# Analog.net
KiCad netlist of a schematic drawn in Altium Designer
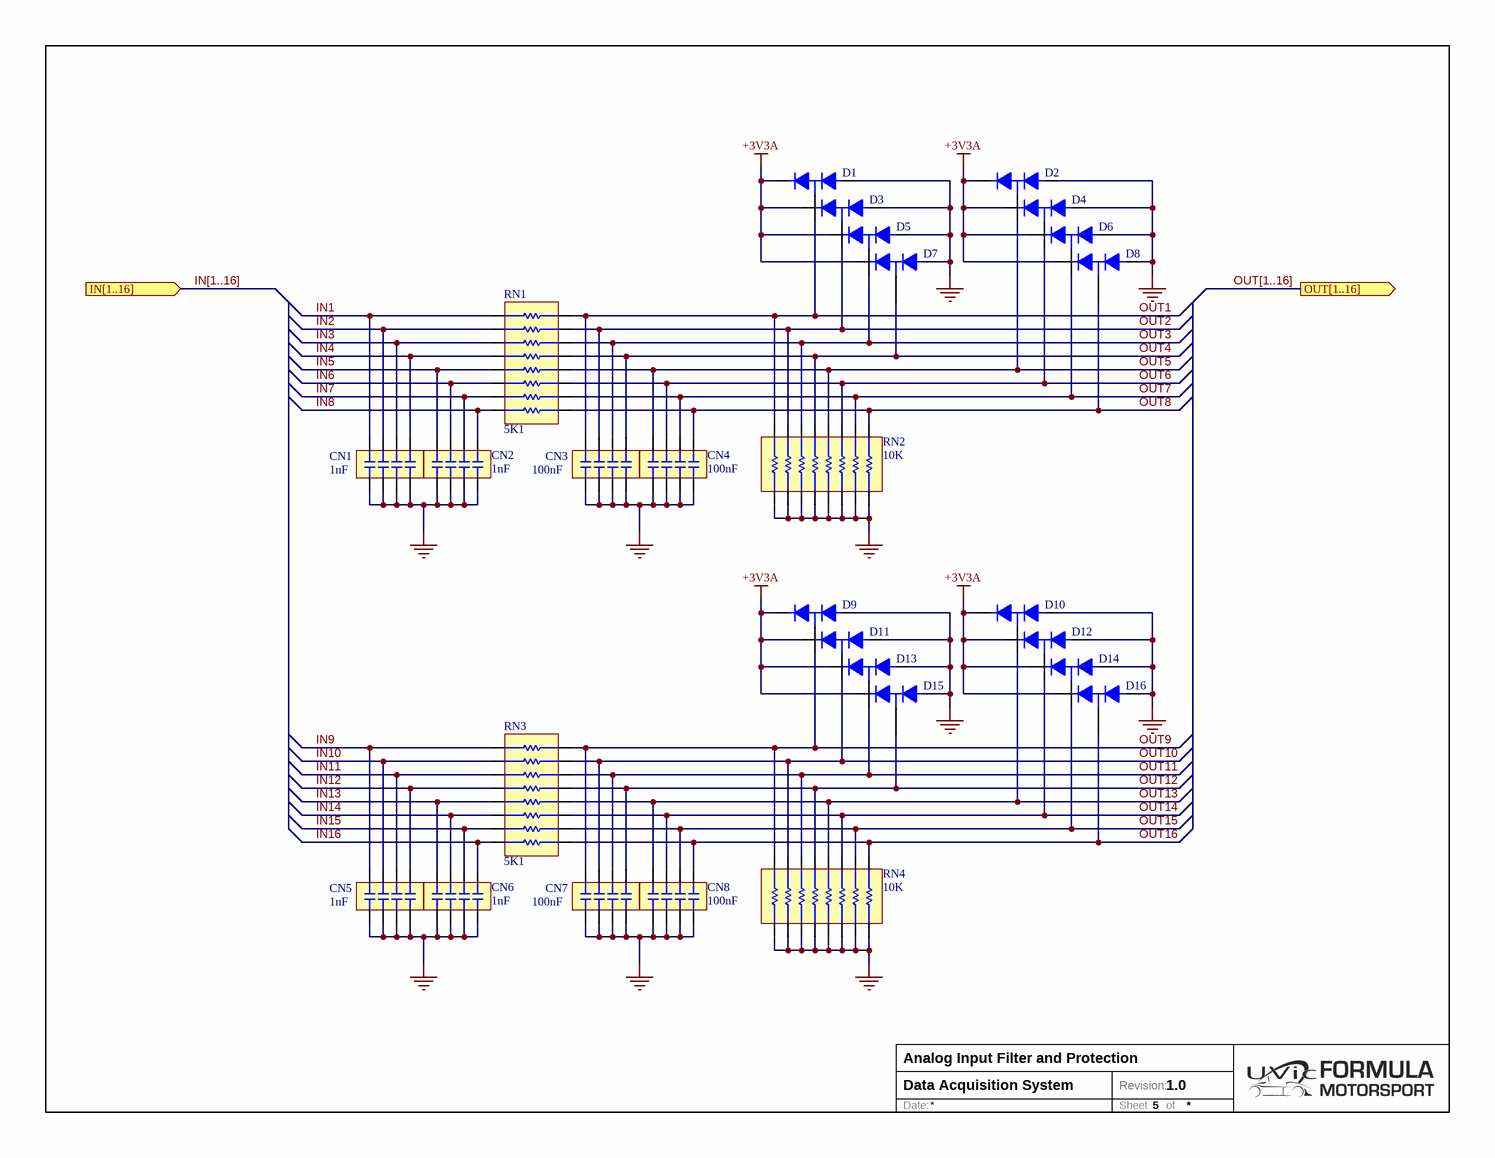
[diagram p0: Analog.SchDoc]

(export (version "E")
  (design (tool "Eeschema 10.0.6"))
  (components
    (comp (ref "CN1")
      (value "1nF")
      (footprint "CAF-80P319X159-8N")
      (description "Capacitor Array - 1nF - 4x - Isolated")
      (fields (field (name "VOLTAGE") "16V") (field (name "Comment") "CKCA43X7R1H102M100AA"))
      (libsource (lib "DAQ") (part "CKCA43X7R1H102M100AA"))
    )
    (comp (ref "CN2")
      (value "1nF")
      (footprint "CAF-80P319X159-8N")
      (description "Capacitor Array - 1nF - 4x - Isolated")
      (fields (field (name "VOLTAGE") "16V") (field (name "Comment") "CKCA43X7R1H102M100AA"))
      (libsource (lib "DAQ") (part "CKCA43X7R1H102M100AA"))
    )
    (comp (ref "CN3")
      (value "100nF")
      (footprint "CAF-80P319X159-8N")
      (description "Capacitor Array - 100nF - 4x - Isolated")
      (fields (field (name "VOLTAGE") "16V") (field (name "Comment") "CKCA43X7R1C104M100AA"))
      (libsource (lib "DAQ") (part "CKCA43X7R1C104M100AA"))
    )
    (comp (ref "CN4")
      (value "100nF")
      (footprint "CAF-80P319X159-8N")
      (description "Capacitor Array - 100nF - 4x - Isolated")
      (fields (field (name "VOLTAGE") "16V") (field (name "Comment") "CKCA43X7R1C104M100AA"))
      (libsource (lib "DAQ") (part "CKCA43X7R1C104M100AA"))
    )
    (comp (ref "CN5")
      (value "1nF")
      (footprint "CAF-80P319X159-8N")
      (description "Capacitor Array - 1nF - 4x - Isolated")
      (fields (field (name "VOLTAGE") "16V") (field (name "Comment") "CKCA43X7R1H102M100AA"))
      (libsource (lib "DAQ") (part "CKCA43X7R1H102M100AA"))
    )
    (comp (ref "CN6")
      (value "1nF")
      (footprint "CAF-80P319X159-8N")
      (description "Capacitor Array - 1nF - 4x - Isolated")
      (fields (field (name "VOLTAGE") "16V") (field (name "Comment") "CKCA43X7R1H102M100AA"))
      (libsource (lib "DAQ") (part "CKCA43X7R1H102M100AA"))
    )
    (comp (ref "CN7")
      (value "100nF")
      (footprint "CAF-80P319X159-8N")
      (description "Capacitor Array - 100nF - 4x - Isolated")
      (fields (field (name "VOLTAGE") "16V") (field (name "Comment") "CKCA43X7R1C104M100AA"))
      (libsource (lib "DAQ") (part "CKCA43X7R1C104M100AA"))
    )
    (comp (ref "CN8")
      (value "100nF")
      (footprint "CAF-80P319X159-8N")
      (description "Capacitor Array - 100nF - 4x - Isolated")
      (fields (field (name "VOLTAGE") "16V") (field (name "Comment") "CKCA43X7R1C104M100AA"))
      (libsource (lib "DAQ") (part "CKCA43X7R1C104M100AA"))
    )
    (comp (ref "D1")
      (value "BAS70-04LT1G")
      (footprint "ONSC-SOT-23-3-318-08_V")
      (description "Schottky Diode Array")
      (libsource (lib "DAQ") (part "BAS70-04LT1G"))
    )
    (comp (ref "D2")
      (value "BAS70-04LT1G")
      (footprint "ONSC-SOT-23-3-318-08_V")
      (description "Schottky Diode Array")
      (libsource (lib "DAQ") (part "BAS70-04LT1G"))
    )
    (comp (ref "D3")
      (value "BAS70-04LT1G")
      (footprint "ONSC-SOT-23-3-318-08_V")
      (description "Schottky Diode Array")
      (libsource (lib "DAQ") (part "BAS70-04LT1G"))
    )
    (comp (ref "D4")
      (value "BAS70-04LT1G")
      (footprint "ONSC-SOT-23-3-318-08_V")
      (description "Schottky Diode Array")
      (libsource (lib "DAQ") (part "BAS70-04LT1G"))
    )
    (comp (ref "D5")
      (value "BAS70-04LT1G")
      (footprint "ONSC-SOT-23-3-318-08_V")
      (description "Schottky Diode Array")
      (libsource (lib "DAQ") (part "BAS70-04LT1G"))
    )
    (comp (ref "D6")
      (value "BAS70-04LT1G")
      (footprint "ONSC-SOT-23-3-318-08_V")
      (description "Schottky Diode Array")
      (libsource (lib "DAQ") (part "BAS70-04LT1G"))
    )
    (comp (ref "D7")
      (value "BAS70-04LT1G")
      (footprint "ONSC-SOT-23-3-318-08_V")
      (description "Schottky Diode Array")
      (libsource (lib "DAQ") (part "BAS70-04LT1G"))
    )
    (comp (ref "D8")
      (value "BAS70-04LT1G")
      (footprint "ONSC-SOT-23-3-318-08_V")
      (description "Schottky Diode Array")
      (libsource (lib "DAQ") (part "BAS70-04LT1G"))
    )
    (comp (ref "D9")
      (value "BAS70-04LT1G")
      (footprint "ONSC-SOT-23-3-318-08_V")
      (description "Schottky Diode Array")
      (libsource (lib "DAQ") (part "BAS70-04LT1G"))
    )
    (comp (ref "D10")
      (value "BAS70-04LT1G")
      (footprint "ONSC-SOT-23-3-318-08_V")
      (description "Schottky Diode Array")
      (libsource (lib "DAQ") (part "BAS70-04LT1G"))
    )
    (comp (ref "D11")
      (value "BAS70-04LT1G")
      (footprint "ONSC-SOT-23-3-318-08_V")
      (description "Schottky Diode Array")
      (libsource (lib "DAQ") (part "BAS70-04LT1G"))
    )
    (comp (ref "D12")
      (value "BAS70-04LT1G")
      (footprint "ONSC-SOT-23-3-318-08_V")
      (description "Schottky Diode Array")
      (libsource (lib "DAQ") (part "BAS70-04LT1G"))
    )
    (comp (ref "D13")
      (value "BAS70-04LT1G")
      (footprint "ONSC-SOT-23-3-318-08_V")
      (description "Schottky Diode Array")
      (libsource (lib "DAQ") (part "BAS70-04LT1G"))
    )
    (comp (ref "D14")
      (value "BAS70-04LT1G")
      (footprint "ONSC-SOT-23-3-318-08_V")
      (description "Schottky Diode Array")
      (libsource (lib "DAQ") (part "BAS70-04LT1G"))
    )
    (comp (ref "D15")
      (value "BAS70-04LT1G")
      (footprint "ONSC-SOT-23-3-318-08_V")
      (description "Schottky Diode Array")
      (libsource (lib "DAQ") (part "BAS70-04LT1G"))
    )
    (comp (ref "D16")
      (value "BAS70-04LT1G")
      (footprint "ONSC-SOT-23-3-318-08_V")
      (description "Schottky Diode Array")
      (libsource (lib "DAQ") (part "BAS70-04LT1G"))
    )
    (comp (ref "RN1")
      (value "5K1")
      (footprint "CAF-80P160X100-8N")
      (description "Resistor Array - 5K1 - x8 - Independent")
      (fields (field (name "TOLERANCE") "5%") (field (name "Comment") "MNR18ERAPJ512"))
      (libsource (lib "DAQ") (part "MNR18ERAPJ512"))
    )
    (comp (ref "RN2")
      (value "10K")
      (footprint "CAF-80P160X100-8N")
      (description "Resistor Array - 10K - x8 - Independent")
      (fields (field (name "TOLERANCE") "5%") (field (name "Comment") "MNR18ERAPJ103"))
      (libsource (lib "DAQ") (part "MNR18ERAPJ103"))
    )
    (comp (ref "RN3")
      (value "5K1")
      (footprint "CAF-80P160X100-8N")
      (description "Resistor Array - 5K1 - x8 - Independent")
      (fields (field (name "TOLERANCE") "5%") (field (name "Comment") "MNR18ERAPJ512"))
      (libsource (lib "DAQ") (part "MNR18ERAPJ512"))
    )
    (comp (ref "RN4")
      (value "10K")
      (footprint "CAF-80P160X100-8N")
      (description "Resistor Array - 10K - x8 - Independent")
      (fields (field (name "TOLERANCE") "5%") (field (name "Comment") "MNR18ERAPJ103"))
      (libsource (lib "DAQ") (part "MNR18ERAPJ103"))
    )
  )
  (nets
    (net (code "1") (name "+3V3A") (class "Default")
      (node (ref "D1") (pin "2") (pinfunction "K_2") (pintype "passive"))
      (node (ref "D10") (pin "2") (pinfunction "K_2") (pintype "passive"))
      (node (ref "D11") (pin "2") (pinfunction "K_2") (pintype "passive"))
      (node (ref "D12") (pin "2") (pinfunction "K_2") (pintype "passive"))
      (node (ref "D13") (pin "2") (pinfunction "K_2") (pintype "passive"))
      (node (ref "D14") (pin "2") (pinfunction "K_2") (pintype "passive"))
      (node (ref "D15") (pin "2") (pinfunction "K_2") (pintype "passive"))
      (node (ref "D16") (pin "2") (pinfunction "K_2") (pintype "passive"))
      (node (ref "D2") (pin "2") (pinfunction "K_2") (pintype "passive"))
      (node (ref "D3") (pin "2") (pinfunction "K_2") (pintype "passive"))
      (node (ref "D4") (pin "2") (pinfunction "K_2") (pintype "passive"))
      (node (ref "D5") (pin "2") (pinfunction "K_2") (pintype "passive"))
      (node (ref "D6") (pin "2") (pinfunction "K_2") (pintype "passive"))
      (node (ref "D7") (pin "2") (pinfunction "K_2") (pintype "passive"))
      (node (ref "D8") (pin "2") (pinfunction "K_2") (pintype "passive"))
      (node (ref "D9") (pin "2") (pinfunction "K_2") (pintype "passive"))
    )
    (net (code "2") (name "/IN1") (class "Default")
      (node (ref "CN1") (pin "8") (pinfunction "8_8") (pintype "passive"))
      (node (ref "RN1") (pin "9") (pinfunction "9_9") (pintype "passive"))
    )
    (net (code "3") (name "/IN2") (class "Default")
      (node (ref "CN1") (pin "7") (pinfunction "7_7") (pintype "passive"))
      (node (ref "RN1") (pin "10") (pinfunction "10_10") (pintype "passive"))
    )
    (net (code "4") (name "/IN3") (class "Default")
      (node (ref "CN1") (pin "6") (pinfunction "6_6") (pintype "passive"))
      (node (ref "RN1") (pin "11") (pinfunction "11_11") (pintype "passive"))
    )
    (net (code "5") (name "/IN4") (class "Default")
      (node (ref "CN1") (pin "5") (pinfunction "5_5") (pintype "passive"))
      (node (ref "RN1") (pin "12") (pinfunction "12_12") (pintype "passive"))
    )
    (net (code "6") (name "/IN5") (class "Default")
      (node (ref "CN2") (pin "8") (pinfunction "8_8") (pintype "passive"))
      (node (ref "RN1") (pin "13") (pinfunction "13_13") (pintype "passive"))
    )
    (net (code "7") (name "/IN6") (class "Default")
      (node (ref "CN2") (pin "7") (pinfunction "7_7") (pintype "passive"))
      (node (ref "RN1") (pin "14") (pinfunction "14_14") (pintype "passive"))
    )
    (net (code "8") (name "/IN7") (class "Default")
      (node (ref "CN2") (pin "6") (pinfunction "6_6") (pintype "passive"))
      (node (ref "RN1") (pin "15") (pinfunction "15_15") (pintype "passive"))
    )
    (net (code "9") (name "/IN8") (class "Default")
      (node (ref "CN2") (pin "5") (pinfunction "5_5") (pintype "passive"))
      (node (ref "RN1") (pin "16") (pinfunction "16_16") (pintype "passive"))
    )
    (net (code "10") (name "/IN9") (class "Default")
      (node (ref "CN5") (pin "8") (pinfunction "8_8") (pintype "passive"))
      (node (ref "RN3") (pin "9") (pinfunction "9_9") (pintype "passive"))
    )
    (net (code "11") (name "/IN10") (class "Default")
      (node (ref "CN5") (pin "7") (pinfunction "7_7") (pintype "passive"))
      (node (ref "RN3") (pin "10") (pinfunction "10_10") (pintype "passive"))
    )
    (net (code "12") (name "/IN11") (class "Default")
      (node (ref "CN5") (pin "6") (pinfunction "6_6") (pintype "passive"))
      (node (ref "RN3") (pin "11") (pinfunction "11_11") (pintype "passive"))
    )
    (net (code "13") (name "/IN12") (class "Default")
      (node (ref "CN5") (pin "5") (pinfunction "5_5") (pintype "passive"))
      (node (ref "RN3") (pin "12") (pinfunction "12_12") (pintype "passive"))
    )
    (net (code "14") (name "/IN13") (class "Default")
      (node (ref "CN6") (pin "8") (pinfunction "8_8") (pintype "passive"))
      (node (ref "RN3") (pin "13") (pinfunction "13_13") (pintype "passive"))
    )
    (net (code "15") (name "/IN14") (class "Default")
      (node (ref "CN6") (pin "7") (pinfunction "7_7") (pintype "passive"))
      (node (ref "RN3") (pin "14") (pinfunction "14_14") (pintype "passive"))
    )
    (net (code "16") (name "/IN15") (class "Default")
      (node (ref "CN6") (pin "6") (pinfunction "6_6") (pintype "passive"))
      (node (ref "RN3") (pin "15") (pinfunction "15_15") (pintype "passive"))
    )
    (net (code "17") (name "/IN16") (class "Default")
      (node (ref "CN6") (pin "5") (pinfunction "5_5") (pintype "passive"))
      (node (ref "RN3") (pin "16") (pinfunction "16_16") (pintype "passive"))
    )
    (net (code "19") (name "/OUT1") (class "Default")
      (node (ref "CN3") (pin "8") (pinfunction "8_8") (pintype "passive"))
      (node (ref "D1") (pin "3") (pinfunction "K/A_3") (pintype "passive"))
      (node (ref "RN1") (pin "8") (pinfunction "8_8") (pintype "passive"))
      (node (ref "RN2") (pin "8") (pinfunction "8_8") (pintype "passive"))
    )
    (net (code "20") (name "/OUT2") (class "Default")
      (node (ref "CN3") (pin "7") (pinfunction "7_7") (pintype "passive"))
      (node (ref "D3") (pin "3") (pinfunction "K/A_3") (pintype "passive"))
      (node (ref "RN1") (pin "7") (pinfunction "7_7") (pintype "passive"))
      (node (ref "RN2") (pin "7") (pinfunction "7_7") (pintype "passive"))
    )
    (net (code "21") (name "/OUT3") (class "Default")
      (node (ref "CN3") (pin "6") (pinfunction "6_6") (pintype "passive"))
      (node (ref "D5") (pin "3") (pinfunction "K/A_3") (pintype "passive"))
      (node (ref "RN1") (pin "6") (pinfunction "6_6") (pintype "passive"))
      (node (ref "RN2") (pin "6") (pinfunction "6_6") (pintype "passive"))
    )
    (net (code "22") (name "/OUT4") (class "Default")
      (node (ref "CN3") (pin "5") (pinfunction "5_5") (pintype "passive"))
      (node (ref "D7") (pin "3") (pinfunction "K/A_3") (pintype "passive"))
      (node (ref "RN1") (pin "5") (pinfunction "5_5") (pintype "passive"))
      (node (ref "RN2") (pin "5") (pinfunction "5_5") (pintype "passive"))
    )
    (net (code "23") (name "/OUT5") (class "Default")
      (node (ref "CN4") (pin "8") (pinfunction "8_8") (pintype "passive"))
      (node (ref "D2") (pin "3") (pinfunction "K/A_3") (pintype "passive"))
      (node (ref "RN1") (pin "4") (pinfunction "4_4") (pintype "passive"))
      (node (ref "RN2") (pin "4") (pinfunction "4_4") (pintype "passive"))
    )
    (net (code "24") (name "/OUT6") (class "Default")
      (node (ref "CN4") (pin "7") (pinfunction "7_7") (pintype "passive"))
      (node (ref "D4") (pin "3") (pinfunction "K/A_3") (pintype "passive"))
      (node (ref "RN1") (pin "3") (pinfunction "3_3") (pintype "passive"))
      (node (ref "RN2") (pin "3") (pinfunction "3_3") (pintype "passive"))
    )
    (net (code "25") (name "/OUT7") (class "Default")
      (node (ref "CN4") (pin "6") (pinfunction "6_6") (pintype "passive"))
      (node (ref "D6") (pin "3") (pinfunction "K/A_3") (pintype "passive"))
      (node (ref "RN1") (pin "2") (pinfunction "2_2") (pintype "passive"))
      (node (ref "RN2") (pin "2") (pinfunction "2_2") (pintype "passive"))
    )
    (net (code "26") (name "/OUT8") (class "Default")
      (node (ref "CN4") (pin "5") (pinfunction "5_5") (pintype "passive"))
      (node (ref "D8") (pin "3") (pinfunction "K/A_3") (pintype "passive"))
      (node (ref "RN1") (pin "1") (pinfunction "1_1") (pintype "passive"))
      (node (ref "RN2") (pin "1") (pinfunction "1_1") (pintype "passive"))
    )
    (net (code "27") (name "/OUT9") (class "Default")
      (node (ref "CN7") (pin "8") (pinfunction "8_8") (pintype "passive"))
      (node (ref "D9") (pin "3") (pinfunction "K/A_3") (pintype "passive"))
      (node (ref "RN3") (pin "8") (pinfunction "8_8") (pintype "passive"))
      (node (ref "RN4") (pin "8") (pinfunction "8_8") (pintype "passive"))
    )
    (net (code "28") (name "/OUT10") (class "Default")
      (node (ref "CN7") (pin "7") (pinfunction "7_7") (pintype "passive"))
      (node (ref "D11") (pin "3") (pinfunction "K/A_3") (pintype "passive"))
      (node (ref "RN3") (pin "7") (pinfunction "7_7") (pintype "passive"))
      (node (ref "RN4") (pin "7") (pinfunction "7_7") (pintype "passive"))
    )
    (net (code "29") (name "/OUT11") (class "Default")
      (node (ref "CN7") (pin "6") (pinfunction "6_6") (pintype "passive"))
      (node (ref "D13") (pin "3") (pinfunction "K/A_3") (pintype "passive"))
      (node (ref "RN3") (pin "6") (pinfunction "6_6") (pintype "passive"))
      (node (ref "RN4") (pin "6") (pinfunction "6_6") (pintype "passive"))
    )
    (net (code "30") (name "/OUT12") (class "Default")
      (node (ref "CN7") (pin "5") (pinfunction "5_5") (pintype "passive"))
      (node (ref "D15") (pin "3") (pinfunction "K/A_3") (pintype "passive"))
      (node (ref "RN3") (pin "5") (pinfunction "5_5") (pintype "passive"))
      (node (ref "RN4") (pin "5") (pinfunction "5_5") (pintype "passive"))
    )
    (net (code "31") (name "/OUT13") (class "Default")
      (node (ref "CN8") (pin "8") (pinfunction "8_8") (pintype "passive"))
      (node (ref "D10") (pin "3") (pinfunction "K/A_3") (pintype "passive"))
      (node (ref "RN3") (pin "4") (pinfunction "4_4") (pintype "passive"))
      (node (ref "RN4") (pin "4") (pinfunction "4_4") (pintype "passive"))
    )
    (net (code "32") (name "/OUT14") (class "Default")
      (node (ref "CN8") (pin "7") (pinfunction "7_7") (pintype "passive"))
      (node (ref "D12") (pin "3") (pinfunction "K/A_3") (pintype "passive"))
      (node (ref "RN3") (pin "3") (pinfunction "3_3") (pintype "passive"))
      (node (ref "RN4") (pin "3") (pinfunction "3_3") (pintype "passive"))
    )
    (net (code "33") (name "/OUT15") (class "Default")
      (node (ref "CN8") (pin "6") (pinfunction "6_6") (pintype "passive"))
      (node (ref "D14") (pin "3") (pinfunction "K/A_3") (pintype "passive"))
      (node (ref "RN3") (pin "2") (pinfunction "2_2") (pintype "passive"))
      (node (ref "RN4") (pin "2") (pinfunction "2_2") (pintype "passive"))
    )
    (net (code "34") (name "/OUT16") (class "Default")
      (node (ref "CN8") (pin "5") (pinfunction "5_5") (pintype "passive"))
      (node (ref "D16") (pin "3") (pinfunction "K/A_3") (pintype "passive"))
      (node (ref "RN3") (pin "1") (pinfunction "1_1") (pintype "passive"))
      (node (ref "RN4") (pin "1") (pinfunction "1_1") (pintype "passive"))
    )
    (net (code "36") (name "GND") (class "Default")
      (node (ref "CN1") (pin "1") (pinfunction "1_1") (pintype "passive"))
      (node (ref "CN1") (pin "2") (pinfunction "2_2") (pintype "passive"))
      (node (ref "CN1") (pin "3") (pinfunction "3_3") (pintype "passive"))
      (node (ref "CN1") (pin "4") (pinfunction "4_4") (pintype "passive"))
      (node (ref "CN2") (pin "1") (pinfunction "1_1") (pintype "passive"))
      (node (ref "CN2") (pin "2") (pinfunction "2_2") (pintype "passive"))
      (node (ref "CN2") (pin "3") (pinfunction "3_3") (pintype "passive"))
      (node (ref "CN2") (pin "4") (pinfunction "4_4") (pintype "passive"))
      (node (ref "CN3") (pin "1") (pinfunction "1_1") (pintype "passive"))
      (node (ref "CN3") (pin "2") (pinfunction "2_2") (pintype "passive"))
      (node (ref "CN3") (pin "3") (pinfunction "3_3") (pintype "passive"))
      (node (ref "CN3") (pin "4") (pinfunction "4_4") (pintype "passive"))
      (node (ref "CN4") (pin "1") (pinfunction "1_1") (pintype "passive"))
      (node (ref "CN4") (pin "2") (pinfunction "2_2") (pintype "passive"))
      (node (ref "CN4") (pin "3") (pinfunction "3_3") (pintype "passive"))
      (node (ref "CN4") (pin "4") (pinfunction "4_4") (pintype "passive"))
      (node (ref "CN5") (pin "1") (pinfunction "1_1") (pintype "passive"))
      (node (ref "CN5") (pin "2") (pinfunction "2_2") (pintype "passive"))
      (node (ref "CN5") (pin "3") (pinfunction "3_3") (pintype "passive"))
      (node (ref "CN5") (pin "4") (pinfunction "4_4") (pintype "passive"))
      (node (ref "CN6") (pin "1") (pinfunction "1_1") (pintype "passive"))
      (node (ref "CN6") (pin "2") (pinfunction "2_2") (pintype "passive"))
      (node (ref "CN6") (pin "3") (pinfunction "3_3") (pintype "passive"))
      (node (ref "CN6") (pin "4") (pinfunction "4_4") (pintype "passive"))
      (node (ref "CN7") (pin "1") (pinfunction "1_1") (pintype "passive"))
      (node (ref "CN7") (pin "2") (pinfunction "2_2") (pintype "passive"))
      (node (ref "CN7") (pin "3") (pinfunction "3_3") (pintype "passive"))
      (node (ref "CN7") (pin "4") (pinfunction "4_4") (pintype "passive"))
      (node (ref "CN8") (pin "1") (pinfunction "1_1") (pintype "passive"))
      (node (ref "CN8") (pin "2") (pinfunction "2_2") (pintype "passive"))
      (node (ref "CN8") (pin "3") (pinfunction "3_3") (pintype "passive"))
      (node (ref "CN8") (pin "4") (pinfunction "4_4") (pintype "passive"))
      (node (ref "D1") (pin "1") (pinfunction "A_1") (pintype "passive"))
      (node (ref "D10") (pin "1") (pinfunction "A_1") (pintype "passive"))
      (node (ref "D11") (pin "1") (pinfunction "A_1") (pintype "passive"))
      (node (ref "D12") (pin "1") (pinfunction "A_1") (pintype "passive"))
      (node (ref "D13") (pin "1") (pinfunction "A_1") (pintype "passive"))
      (node (ref "D14") (pin "1") (pinfunction "A_1") (pintype "passive"))
      (node (ref "D15") (pin "1") (pinfunction "A_1") (pintype "passive"))
      (node (ref "D16") (pin "1") (pinfunction "A_1") (pintype "passive"))
      (node (ref "D2") (pin "1") (pinfunction "A_1") (pintype "passive"))
      (node (ref "D3") (pin "1") (pinfunction "A_1") (pintype "passive"))
      (node (ref "D4") (pin "1") (pinfunction "A_1") (pintype "passive"))
      (node (ref "D5") (pin "1") (pinfunction "A_1") (pintype "passive"))
      (node (ref "D6") (pin "1") (pinfunction "A_1") (pintype "passive"))
      (node (ref "D7") (pin "1") (pinfunction "A_1") (pintype "passive"))
      (node (ref "D8") (pin "1") (pinfunction "A_1") (pintype "passive"))
      (node (ref "D9") (pin "1") (pinfunction "A_1") (pintype "passive"))
      (node (ref "RN2") (pin "10") (pinfunction "10_10") (pintype "passive"))
      (node (ref "RN2") (pin "11") (pinfunction "11_11") (pintype "passive"))
      (node (ref "RN2") (pin "12") (pinfunction "12_12") (pintype "passive"))
      (node (ref "RN2") (pin "13") (pinfunction "13_13") (pintype "passive"))
      (node (ref "RN2") (pin "14") (pinfunction "14_14") (pintype "passive"))
      (node (ref "RN2") (pin "15") (pinfunction "15_15") (pintype "passive"))
      (node (ref "RN2") (pin "16") (pinfunction "16_16") (pintype "passive"))
      (node (ref "RN2") (pin "9") (pinfunction "9_9") (pintype "passive"))
      (node (ref "RN4") (pin "10") (pinfunction "10_10") (pintype "passive"))
      (node (ref "RN4") (pin "11") (pinfunction "11_11") (pintype "passive"))
      (node (ref "RN4") (pin "12") (pinfunction "12_12") (pintype "passive"))
      (node (ref "RN4") (pin "13") (pinfunction "13_13") (pintype "passive"))
      (node (ref "RN4") (pin "14") (pinfunction "14_14") (pintype "passive"))
      (node (ref "RN4") (pin "15") (pinfunction "15_15") (pintype "passive"))
      (node (ref "RN4") (pin "16") (pinfunction "16_16") (pintype "passive"))
      (node (ref "RN4") (pin "9") (pinfunction "9_9") (pintype "passive"))
    )
  )
)
